# AirU_v2_1.net
KiCad netlist of a schematic drawn in EAGLE
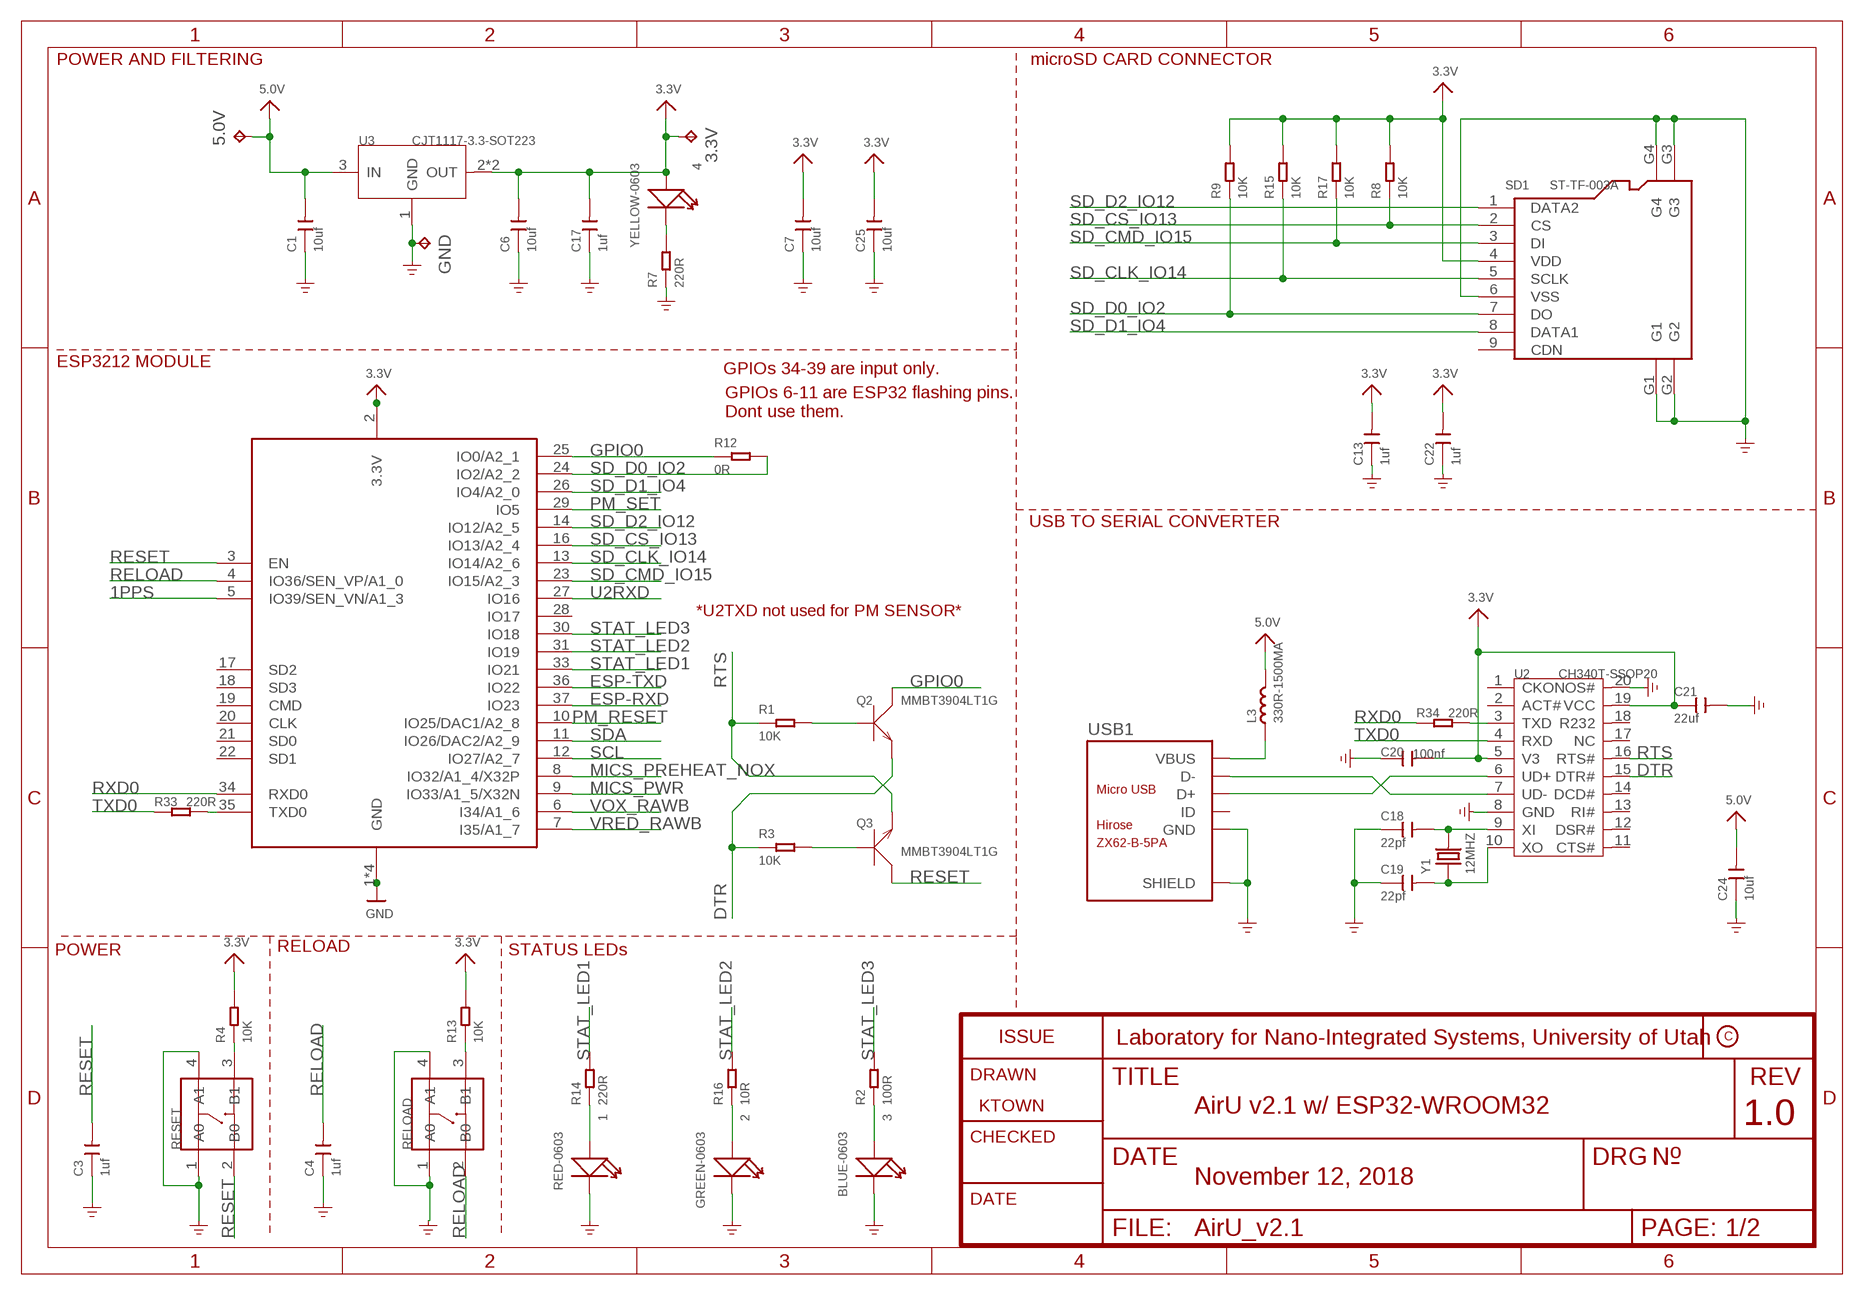
[diagram p0: schematic, sheet 1]
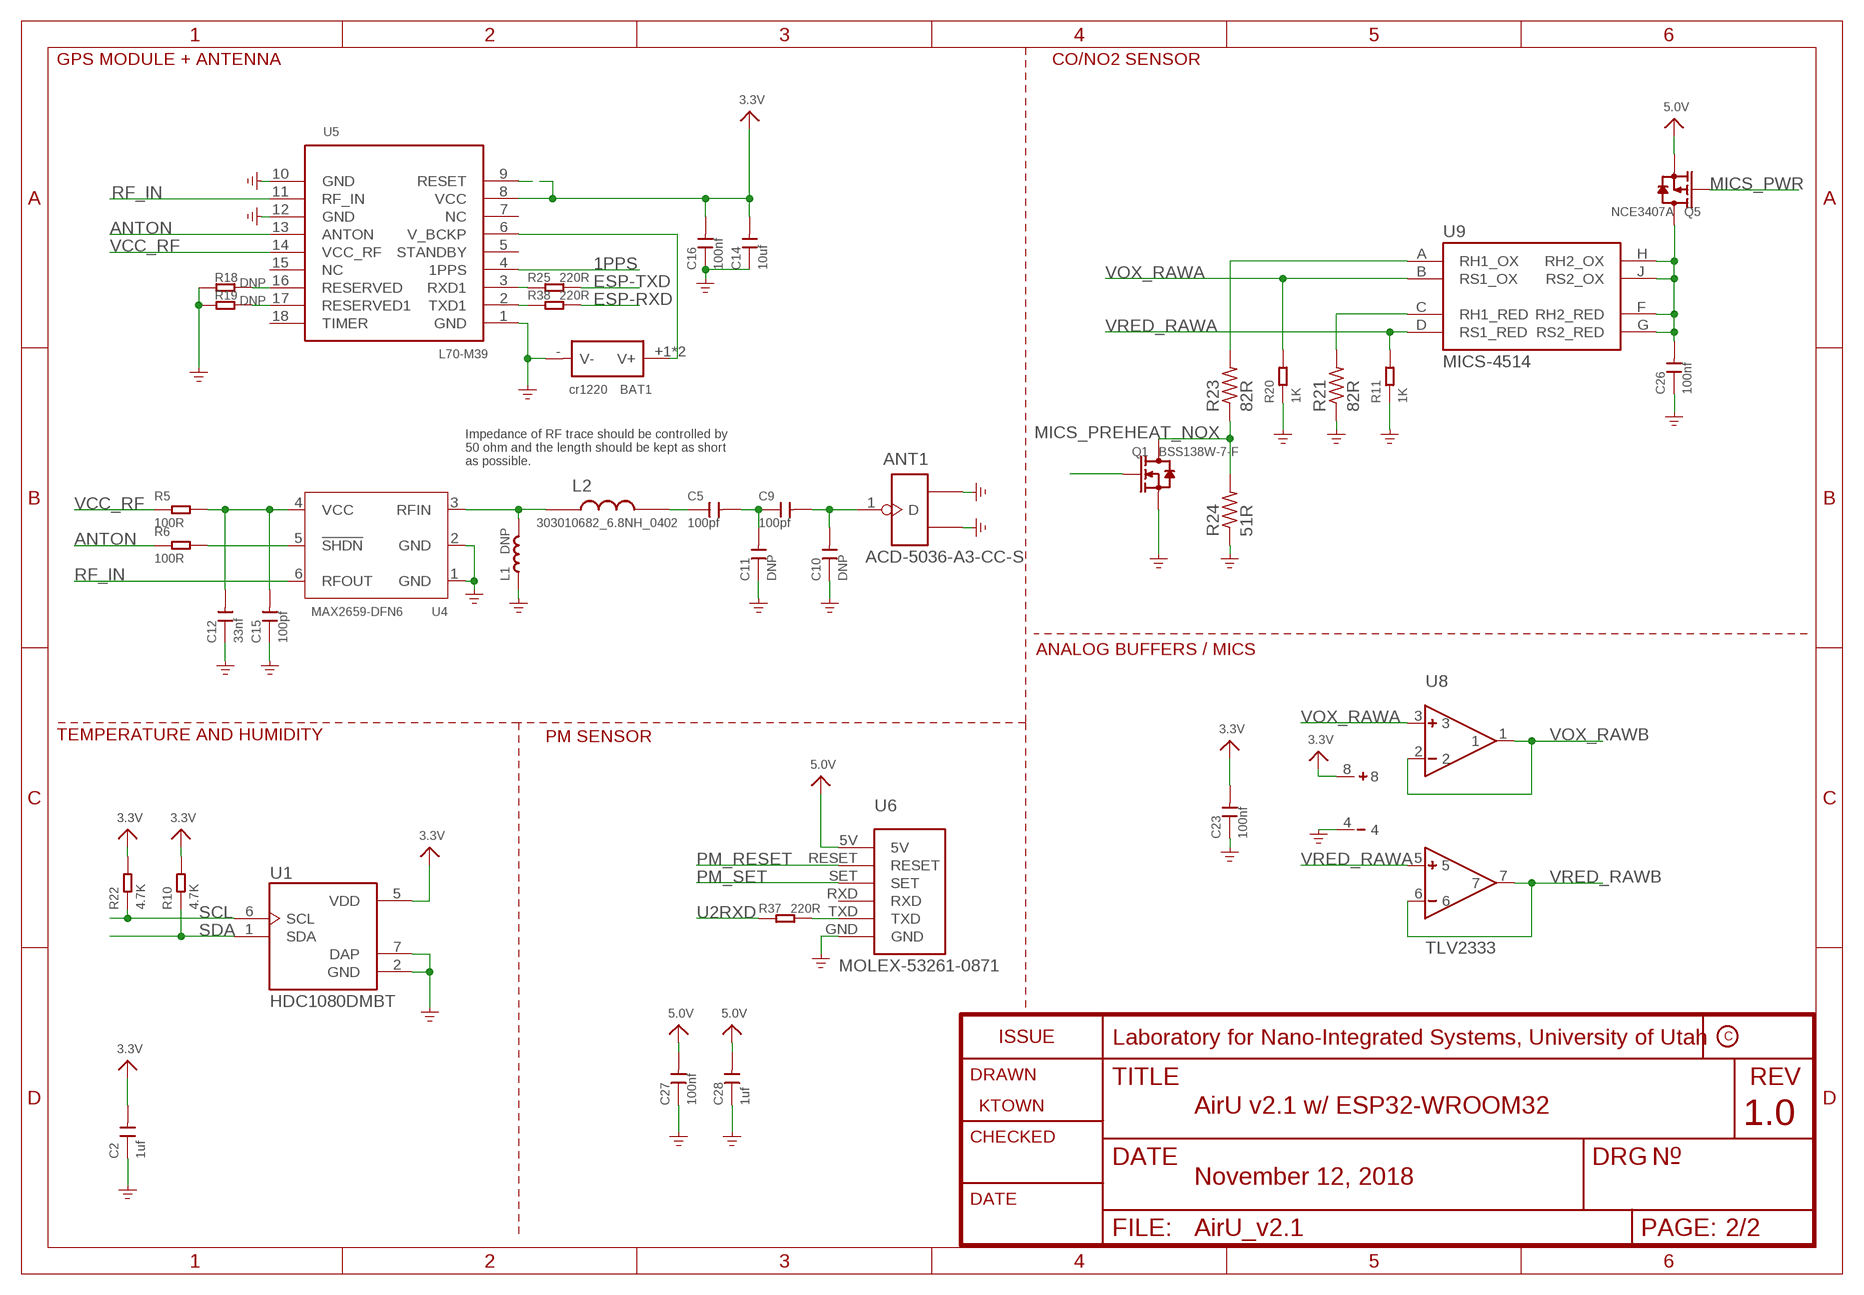
[diagram p1: schematic, sheet 2]

(export (version "E")
  (design (tool "Eeschema 10.0.6"))
  (components
    (comp (ref "1")
      (value "RED-0603")
      (footprint "eagle-import:LED-0603")
      (fields (field (name "MPN") "19-217-R6C-AL1M2VY-3T"))
      (libsource (lib "eagle-import") (part "LED-SMD-RED-DIFFUSED(0603)"))
    )
    (comp (ref "2")
      (value "GREEN-0603")
      (footprint "eagle-import:LED-0603")
      (fields (field (name "MPN") "19-217-G7C-AN1P2-3T"))
      (libsource (lib "eagle-import") (part "SMD-LED-CLEAR-GREEN(0603)"))
    )
    (comp (ref "3")
      (value "BLUE-0603")
      (footprint "eagle-import:LED-0603")
      (fields (field (name "MPN") "19-217-BHC-ZL1M2RY-3T"))
      (libsource (lib "eagle-import") (part "SMD-LED-CLEAR-BLUE(0603)"))
    )
    (comp (ref "3.3V")
      (value "TPTP20SQ")
      (footprint "eagle-import:TP20SQ")
      (libsource (lib "eagle-import") (part "TPTP20SQ"))
    )
    (comp (ref "4")
      (value "YELLOW-0603")
      (footprint "eagle-import:LED-0603")
      (fields (field (name "MPN") "19-217-Y5C-AM1N1VY-3T"))
      (libsource (lib "eagle-import") (part "SMD-LED-CLEAR-YELLOW(0603)"))
    )
    (comp (ref "5.0V")
      (value "TPTP20SQ")
      (footprint "eagle-import:TP20SQ")
      (libsource (lib "eagle-import") (part "TPTP20SQ"))
    )
    (comp (ref "C1")
      (value "10uf")
      (footprint "eagle-import:C0603")
      (fields (field (name "MPN") "CC0603KRX5R6BB106"))
      (libsource (lib "eagle-import") (part "CERAMIC-10UF-10V-10%-X5R(0603)"))
    )
    (comp (ref "C3")
      (value "1uf")
      (footprint "eagle-import:C0603")
      (fields (field (name "MPN") "CC0603KRX7R8BB105"))
      (libsource (lib "eagle-import") (part "CERAMIC-1UF-25V-10%-X7R(0603)"))
    )
    (comp (ref "C4")
      (value "1uf")
      (footprint "eagle-import:C0603")
      (fields (field (name "MPN") "CC0603KRX7R8BB105"))
      (libsource (lib "eagle-import") (part "CERAMIC-1UF-25V-10%-X7R(0603)"))
    )
    (comp (ref "C6")
      (value "10uf")
      (footprint "eagle-import:C0603")
      (fields (field (name "MPN") "CC0603KRX5R6BB106"))
      (libsource (lib "eagle-import") (part "CERAMIC-10UF-10V-10%-X5R(0603)"))
    )
    (comp (ref "C7")
      (value "10uf")
      (footprint "eagle-import:C0603")
      (fields (field (name "MPN") "CC0603KRX5R6BB106"))
      (libsource (lib "eagle-import") (part "CERAMIC-10UF-10V-10%-X5R(0603)"))
    )
    (comp (ref "C13")
      (value "1uf")
      (footprint "eagle-import:C0603")
      (fields (field (name "MPN") "CC0603KRX7R8BB105"))
      (libsource (lib "eagle-import") (part "CERAMIC-1UF-25V-10%-X7R(0603)"))
    )
    (comp (ref "C17")
      (value "1uf")
      (footprint "eagle-import:C0603")
      (fields (field (name "MPN") "CC0603KRX7R8BB105"))
      (libsource (lib "eagle-import") (part "CERAMIC-1UF-25V-10%-X7R(0603)"))
    )
    (comp (ref "C18")
      (value "22pf")
      (footprint "eagle-import:C0603")
      (fields (field (name "MPN") "CC0603JRNPO9BN220"))
      (libsource (lib "eagle-import") (part "CERAMIC-22PF-50V-5%-NPO(0603)"))
    )
    (comp (ref "C19")
      (value "22pf")
      (footprint "eagle-import:C0603")
      (fields (field (name "MPN") "CC0603JRNPO9BN220"))
      (libsource (lib "eagle-import") (part "CERAMIC-22PF-50V-5%-NPO(0603)"))
    )
    (comp (ref "C20")
      (value "100nf")
      (footprint "eagle-import:C0603")
      (fields (field (name "MPN") "CC0603KRX7R9BB104"))
      (libsource (lib "eagle-import") (part "CERAMIC-100NF-50V-10%-X7R(0603)"))
    )
    (comp (ref "C21")
      (value "22uf")
      (footprint "eagle-import:C0805")
      (fields (field (name "MPN") "CC0805MKX5R5BB226"))
      (libsource (lib "eagle-import") (part "CERAMIC-22UF-6.3V-20%-X5R(0805)"))
    )
    (comp (ref "C22")
      (value "1uf")
      (footprint "eagle-import:C0603")
      (fields (field (name "MPN") "CC0603KRX7R8BB105"))
      (libsource (lib "eagle-import") (part "CERAMIC-1UF-25V-10%-X7R(0603)"))
    )
    (comp (ref "C24")
      (value "10uf")
      (footprint "eagle-import:C0603")
      (fields (field (name "MPN") "CC0603KRX5R6BB106"))
      (libsource (lib "eagle-import") (part "CERAMIC-10UF-10V-10%-X5R(0603)"))
    )
    (comp (ref "C25")
      (value "10uf")
      (footprint "eagle-import:C0603")
      (fields (field (name "MPN") "CC0603KRX5R6BB106"))
      (libsource (lib "eagle-import") (part "CERAMIC-10UF-10V-10%-X5R(0603)"))
    )
    (comp (ref "GND")
      (value "TPTP20SQ")
      (footprint "eagle-import:TP20SQ")
      (libsource (lib "eagle-import") (part "TPTP20SQ"))
    )
    (comp (ref "L3")
      (value "330R-1500MA")
      (footprint "eagle-import:L0805")
      (fields (field (name "MPN") "BLM21PG331SN1D"))
      (libsource (lib "eagle-import") (part "SMD-FERRITE-BEAD-330R-1500MA(0805)'0805'"))
    )
    (comp (ref "Q2")
      (value "MMBT3904LT1G")
      (footprint "eagle-import:SOT-23")
      (libsource (lib "eagle-import") (part "SMD-TRANSISTORS-NPN-40V-200MA-MMBT3904LT1G(SOT-23)"))
    )
    (comp (ref "Q3")
      (value "MMBT3904LT1G")
      (footprint "eagle-import:SOT-23")
      (libsource (lib "eagle-import") (part "SMD-TRANSISTORS-NPN-40V-200MA-MMBT3904LT1G(SOT-23)"))
    )
    (comp (ref "R1")
      (value "10K")
      (footprint "eagle-import:R0603")
      (fields (field (name "MPN") "RC0603FR-0710KL"))
      (libsource (lib "eagle-import") (part "SMD-RES-10K-1%-1/10W(0603)"))
    )
    (comp (ref "R2")
      (value "100R")
      (footprint "eagle-import:R0603")
      (fields (field (name "MPN") "RC0603JR-07100RL"))
      (libsource (lib "eagle-import") (part "SMD-RES-100R-5%-1/10W(0603)"))
    )
    (comp (ref "R3")
      (value "10K")
      (footprint "eagle-import:R0603")
      (fields (field (name "MPN") "RC0603FR-0710KL"))
      (libsource (lib "eagle-import") (part "SMD-RES-10K-1%-1/10W(0603)"))
    )
    (comp (ref "R4")
      (value "10K")
      (footprint "eagle-import:R0603")
      (fields (field (name "MPN") "RC0603FR-0710KL"))
      (libsource (lib "eagle-import") (part "SMD-RES-10K-1%-1/10W(0603)"))
    )
    (comp (ref "R7")
      (value "220R")
      (footprint "eagle-import:R0603")
      (fields (field (name "MPN") "RC0603JR-07220RL"))
      (libsource (lib "eagle-import") (part "SMD-RES-220R-5%-1/10W(0603)"))
    )
    (comp (ref "R8")
      (value "10K")
      (footprint "eagle-import:R0603")
      (fields (field (name "MPN") "RC0603FR-0710KL"))
      (libsource (lib "eagle-import") (part "SMD-RES-10K-1%-1/10W(0603)"))
    )
    (comp (ref "R9")
      (value "10K")
      (footprint "eagle-import:R0603")
      (fields (field (name "MPN") "RC0603FR-0710KL"))
      (libsource (lib "eagle-import") (part "SMD-RES-10K-1%-1/10W(0603)"))
    )
    (comp (ref "R12")
      (value "0R")
      (footprint "eagle-import:R0603")
      (fields (field (name "MPN") "RC0603JR-070RL"))
      (libsource (lib "eagle-import") (part "SMD-RES-0R-5%-1/10W(0603)"))
    )
    (comp (ref "R13")
      (value "10K")
      (footprint "eagle-import:R0603")
      (fields (field (name "MPN") "RC0603FR-0710KL"))
      (libsource (lib "eagle-import") (part "SMD-RES-10K-1%-1/10W(0603)"))
    )
    (comp (ref "R14")
      (value "220R")
      (footprint "eagle-import:R0603")
      (fields (field (name "MPN") "RC0603JR-07220RL"))
      (libsource (lib "eagle-import") (part "SMD-RES-220R-5%-1/10W(0603)"))
    )
    (comp (ref "R15")
      (value "10K")
      (footprint "eagle-import:R0603")
      (fields (field (name "MPN") "RC0603FR-0710KL"))
      (libsource (lib "eagle-import") (part "SMD-RES-10K-1%-1/10W(0603)"))
    )
    (comp (ref "R16")
      (value "10R")
      (footprint "eagle-import:R0603")
      (fields (field (name "MPN") "RC0603JR-0710RL"))
      (libsource (lib "eagle-import") (part "SMD-RES-10R-5%-1/10W(0603)"))
    )
    (comp (ref "R17")
      (value "10K")
      (footprint "eagle-import:R0603")
      (fields (field (name "MPN") "RC0603FR-0710KL"))
      (libsource (lib "eagle-import") (part "SMD-RES-10K-1%-1/10W(0603)"))
    )
    (comp (ref "R33")
      (value "220R")
      (footprint "eagle-import:R0603")
      (fields (field (name "MPN") "RC0603JR-07220RL"))
      (libsource (lib "eagle-import") (part "SMD-RES-220R-5%-1/10W(0603)"))
    )
    (comp (ref "R34")
      (value "220R")
      (footprint "eagle-import:R0603")
      (fields (field (name "MPN") "RC0603JR-07220RL"))
      (libsource (lib "eagle-import") (part "SMD-RES-220R-5%-1/10W(0603)"))
    )
    (comp (ref "RELOAD")
      (value "DIP-SWITCH-TACTILE-SPST-NO/TS-1109(4P-D6.0MM)'TS-1109'")
      (footprint "eagle-import:SW4-6.0X6.0X5.0MM")
      (libsource (lib "eagle-import") (part "DIP-SWITCH-TACTILE-SPST-NO/TS-1109(4P-D6.0MM)'TS-1109'"))
    )
    (comp (ref "RESET")
      (value "DIP-SWITCH-TACTILE-SPST-NO/TS-1109(4P-D6.0MM)'TS-1109'")
      (footprint "eagle-import:SW4-6.0X6.0X5.0MM")
      (libsource (lib "eagle-import") (part "DIP-SWITCH-TACTILE-SPST-NO/TS-1109(4P-D6.0MM)'TS-1109'"))
    )
    (comp (ref "SD1")
      (value "ST-TF-003A")
      (footprint "eagle-import:MICRO-SD9+4P-SMD-16.1X14.5X1.85MM")
      (libsource (lib "eagle-import") (part "MICRO-SD-CARD-SOCKET-9P(ST-TF-003A)"))
    )
    (comp (ref "U2")
      (value "CH340T-SSOP20")
      (footprint "eagle-import:SSOP20-0.65-7.6X5.2MM")
      (fields (field (name "MPN") "CH340T"))
      (libsource (lib "eagle-import") (part "INTERFACE-CH340T(SSOP20)"))
    )
    (comp (ref "U3")
      (value "CJT1117-3.3-SOT223")
      (footprint "eagle-import:SOT-223")
      (fields (field (name "MPN") "CJT1117-3.3"))
      (libsource (lib "eagle-import") (part "PMIC-CJT1117-3.3(SOT223)"))
    )
    (comp (ref "U7")
      (value "ESP32_WROOM32_SKINNY")
      (footprint "eagle-import:WROOM32_SKINNY")
      (libsource (lib "eagle-import") (part "ESP32_WROOM32_SKINNY"))
    )
    (comp (ref "USB1")
      (value "ZX62-B-5PA")
      (footprint "eagle-import:MICRO-USB5+6P-SMD-0.65-AB")
      (libsource (lib "eagle-import") (part "MICRO-USB-SMD(ZX62-B-5PA)"))
    )
    (comp (ref "Y1")
      (value "12MHZ")
      (footprint "eagle-import:X2-SMD-5.0X3.2X1.3MM")
      (fields (field (name "MPN") "5032/2P"))
      (libsource (lib "eagle-import") (part "SMD-CRYSTAL-12MHZ-20PF-20PPM-40R(2P-5.0X3.2MM)"))
    )
    (comp (ref "ANT1")
      (value "ACD-5036-A3-CC-S")
      (footprint "eagle-import:ANT3-SMD-5.2X3.7X0.7MM")
      (libsource (lib "eagle-import") (part "ANTENNA-ACD5036"))
    )
    (comp (ref "BAT1")
      (value "cr1220")
      (footprint "eagle-import:BAT2P-13.5-CR1220")
      (libsource (lib "eagle-import") (part "DIP-BATTERY-CELL-HOLDER(1220)"))
    )
    (comp (ref "C2")
      (value "1uf")
      (footprint "eagle-import:C0603")
      (fields (field (name "MPN") "CC0603KRX7R8BB105"))
      (libsource (lib "eagle-import") (part "CERAMIC-1UF-25V-10%-X7R(0603)"))
    )
    (comp (ref "C5")
      (value "100pf")
      (footprint "eagle-import:C0603")
      (fields (field (name "MPN") "CC0603JRNPO9BN101"))
      (libsource (lib "eagle-import") (part "CERAMIC-100PF-50V-5%-NPO(0603)"))
    )
    (comp (ref "C9")
      (value "100pf")
      (footprint "eagle-import:C0603")
      (fields (field (name "MPN") "CC0603JRNPO9BN101"))
      (libsource (lib "eagle-import") (part "CERAMIC-100PF-50V-5%-NPO(0603)"))
    )
    (comp (ref "C10")
      (value "DNP")
      (footprint "eagle-import:C0603")
      (fields (field (name "MPN") "CC0603JRNPO9BN101"))
      (libsource (lib "eagle-import") (part "CERAMIC-100PF-50V-5%-NPO(0603)"))
    )
    (comp (ref "C11")
      (value "DNP")
      (footprint "eagle-import:C0603")
      (fields (field (name "MPN") "CC0603JRNPO9BN101"))
      (libsource (lib "eagle-import") (part "CERAMIC-100PF-50V-5%-NPO(0603)"))
    )
    (comp (ref "C12")
      (value "33nf")
      (footprint "eagle-import:C0603")
      (fields (field (name "MPN") "CC0603KRX7R9BB333"))
      (libsource (lib "eagle-import") (part "CERAMIC-33NF-50V-10%-X7R(0603)"))
    )
    (comp (ref "C14")
      (value "10uf")
      (footprint "eagle-import:C0603")
      (fields (field (name "MPN") "CC0603KRX5R6BB106"))
      (libsource (lib "eagle-import") (part "CERAMIC-10UF-10V-10%-X5R(0603)"))
    )
    (comp (ref "C15")
      (value "100pf")
      (footprint "eagle-import:C0603")
      (fields (field (name "MPN") "CC0603JRNPO9BN101"))
      (libsource (lib "eagle-import") (part "CERAMIC-100PF-50V-5%-NPO(0603)"))
    )
    (comp (ref "C16")
      (value "100nf")
      (footprint "eagle-import:C0603")
      (fields (field (name "MPN") "CC0603KRX7R9BB104"))
      (libsource (lib "eagle-import") (part "CERAMIC-100NF-50V-10%-X7R(0603)"))
    )
    (comp (ref "C23")
      (value "100nf")
      (footprint "eagle-import:C0603")
      (fields (field (name "MPN") "CC0603KRX7R9BB104"))
      (libsource (lib "eagle-import") (part "CERAMIC-100NF-50V-10%-X7R(0603)"))
    )
    (comp (ref "C26")
      (value "100nf")
      (footprint "eagle-import:C0603")
      (fields (field (name "MPN") "CC0603KRX7R9BB104"))
      (libsource (lib "eagle-import") (part "CERAMIC-100NF-50V-10%-X7R(0603)"))
    )
    (comp (ref "C27")
      (value "100nf")
      (footprint "eagle-import:C0603")
      (fields (field (name "MPN") "CC0603KRX7R9BB104"))
      (libsource (lib "eagle-import") (part "CERAMIC-100NF-50V-10%-X7R(0603)"))
    )
    (comp (ref "C28")
      (value "1uf")
      (footprint "eagle-import:C0603")
      (fields (field (name "MPN") "CC0603KRX7R8BB105"))
      (libsource (lib "eagle-import") (part "CERAMIC-1UF-25V-10%-X7R(0603)"))
    )
    (comp (ref "L1")
      (value "DNP")
      (footprint "eagle-import:L0201")
      (libsource (lib "eagle-import") (part "INDUCTOR/FERRITE-BEAD-0201"))
    )
    (comp (ref "L2")
      (value "303010682_6.8NH_0402")
      (footprint "eagle-import:L0402")
      (libsource (lib "eagle-import") (part "303010682_6.8NH_0402"))
    )
    (comp (ref "Q1")
      (value "BSS138W-7-F")
      (footprint "eagle-import:SOT-23")
      (libsource (lib "eagle-import") (part "SMD-MOSFET-N-CH-50V-200MA-BSS138W-7-F(SOT-23)"))
    )
    (comp (ref "Q5")
      (value "NCE3407A")
      (footprint "eagle-import:SOT-23")
      (libsource (lib "eagle-import") (part "SMD-MOSFET-P-CH-VDC=30V-ID=4.3A-NCE3407A(SOT-23)"))
    )
    (comp (ref "R5")
      (value "100R")
      (footprint "eagle-import:R0603")
      (fields (field (name "MPN") "RC0603JR-07100RL"))
      (libsource (lib "eagle-import") (part "SMD-RES-100R-5%-1/10W(0603)"))
    )
    (comp (ref "R6")
      (value "100R")
      (footprint "eagle-import:R0603")
      (fields (field (name "MPN") "RC0603JR-07100RL"))
      (libsource (lib "eagle-import") (part "SMD-RES-100R-5%-1/10W(0603)"))
    )
    (comp (ref "R10")
      (value "4.7K")
      (footprint "eagle-import:R0603")
      (fields (field (name "MPN") "RC0603JR-074K7L"))
      (libsource (lib "eagle-import") (part "SMD-RES-4.7K-5%-1/10W(0603)"))
    )
    (comp (ref "R11")
      (value "1K")
      (footprint "eagle-import:R0603")
      (fields (field (name "MPN") "RC0603FR-071KL"))
      (libsource (lib "eagle-import") (part "SMD-RES-1K-1%-1/10W(0603)"))
    )
    (comp (ref "R18")
      (value "DNP")
      (footprint "eagle-import:R0603")
      (fields (field (name "MPN") "RC0603FR-0710KL"))
      (libsource (lib "eagle-import") (part "SMD-RES-10K-1%-1/10W(0603)"))
    )
    (comp (ref "R19")
      (value "DNP")
      (footprint "eagle-import:R0603")
      (fields (field (name "MPN") "RC0603FR-0710KL"))
      (libsource (lib "eagle-import") (part "SMD-RES-10K-1%-1/10W(0603)"))
    )
    (comp (ref "R20")
      (value "1K")
      (footprint "eagle-import:R0603")
      (fields (field (name "MPN") "RC0603FR-071KL"))
      (libsource (lib "eagle-import") (part "SMD-RES-1K-1%-1/10W(0603)"))
    )
    (comp (ref "R21")
      (value "82R")
      (footprint "eagle-import:R0603")
      (libsource (lib "eagle-import") (part "R-US_R0603"))
    )
    (comp (ref "R22")
      (value "4.7K")
      (footprint "eagle-import:R0603")
      (fields (field (name "MPN") "RC0603JR-074K7L"))
      (libsource (lib "eagle-import") (part "SMD-RES-4.7K-5%-1/10W(0603)"))
    )
    (comp (ref "R23")
      (value "82R")
      (footprint "eagle-import:R0603")
      (libsource (lib "eagle-import") (part "R-US_R0603"))
    )
    (comp (ref "R24")
      (value "51R")
      (footprint "eagle-import:R0603")
      (libsource (lib "eagle-import") (part "R-US_R0603"))
    )
    (comp (ref "R25")
      (value "220R")
      (footprint "eagle-import:R0603")
      (fields (field (name "MPN") "RC0603JR-07220RL"))
      (libsource (lib "eagle-import") (part "SMD-RES-220R-5%-1/10W(0603)"))
    )
    (comp (ref "R37")
      (value "220R")
      (footprint "eagle-import:R0603")
      (fields (field (name "MPN") "RC0603JR-07220RL"))
      (libsource (lib "eagle-import") (part "SMD-RES-220R-5%-1/10W(0603)"))
    )
    (comp (ref "R38")
      (value "220R")
      (footprint "eagle-import:R0603")
      (fields (field (name "MPN") "RC0603JR-07220RL"))
      (libsource (lib "eagle-import") (part "SMD-RES-220R-5%-1/10W(0603)"))
    )
    (comp (ref "U1")
      (value "HDC1080DMBT")
      (footprint "eagle-import:SON100P300X300X80-7N")
      (fields (field (name "DIGI-KEY_PART_NUMBER") "296-43864-1-ND") (field (name "MF") "Texas Instruments"))
      (libsource (lib "eagle-import") (part "HDC1080DMBT"))
    )
    (comp (ref "U4")
      (value "MAX2659-DFN6")
      (footprint "eagle-import:DFN6-0.5-1.5X1.2X0.72MM")
      (fields (field (name "MPN") "MAX2659"))
      (libsource (lib "eagle-import") (part "AMPLIFIER-MAX2659"))
    )
    (comp (ref "U5")
      (value "L70-M39")
      (footprint "eagle-import:LGA18-1.1-9.7X10.1X2.5MM")
      (fields (field (name "MPN") "L70"))
      (libsource (lib "eagle-import") (part "MOUDLE-GPS-L70-HARDWARE"))
    )
    (comp (ref "U6")
      (value "MOLEX-53261-0871")
      (footprint "eagle-import:MOLEX-53261-0871")
      (libsource (lib "eagle-import") (part "MOLEX-53261-0871"))
    )
    (comp (ref "U8")
      (value "TLV2333")
      (footprint "eagle-import:TLV2333")
      (libsource (lib "eagle-import") (part "TLV2333"))
    )
    (comp (ref "U9")
      (value "MICS-4514")
      (footprint "eagle-import:MICS_10-SMD")
      (fields (field (name "MF") "Amphenol"))
      (libsource (lib "eagle-import") (part "MICS-4514"))
    )
  )
  (nets
    (net (code "1") (name "1PPS") (class "Default")
      (node (ref "U5") (pin "4") (pinfunction "1PPS_4") (pintype "bidirectional"))
      (node (ref "U7") (pin "5") (pinfunction "IO39/SEN_VN/A1_3_5") (pintype "passive"))
    )
    (net (code "2") (name "3.3V") (class "Default")
      (node (ref "3.3V") (pin "TP") (pinfunction "TP_TP") (pintype "input"))
      (node (ref "4") (pin "+") (pinfunction "+_+") (pintype "passive"))
      (node (ref "C13") (pin "2") (pinfunction "2_2") (pintype "passive"))
      (node (ref "C14") (pin "2") (pinfunction "2_2") (pintype "passive"))
      (node (ref "C16") (pin "2") (pinfunction "2_2") (pintype "passive"))
      (node (ref "C17") (pin "2") (pinfunction "2_2") (pintype "passive"))
      (node (ref "C2") (pin "2") (pinfunction "2_2") (pintype "passive"))
      (node (ref "C20") (pin "2") (pinfunction "2_2") (pintype "passive"))
      (node (ref "C21") (pin "1") (pinfunction "1_1") (pintype "passive"))
      (node (ref "C22") (pin "2") (pinfunction "2_2") (pintype "passive"))
      (node (ref "C23") (pin "2") (pinfunction "2_2") (pintype "passive"))
      (node (ref "C25") (pin "2") (pinfunction "2_2") (pintype "passive"))
      (node (ref "C6") (pin "2") (pinfunction "2_2") (pintype "passive"))
      (node (ref "C7") (pin "2") (pinfunction "2_2") (pintype "passive"))
      (node (ref "R10") (pin "2") (pinfunction "2_2") (pintype "passive"))
      (node (ref "R13") (pin "2") (pinfunction "2_2") (pintype "passive"))
      (node (ref "R15") (pin "2") (pinfunction "2_2") (pintype "passive"))
      (node (ref "R17") (pin "2") (pinfunction "2_2") (pintype "passive"))
      (node (ref "R22") (pin "2") (pinfunction "2_2") (pintype "passive"))
      (node (ref "R4") (pin "2") (pinfunction "2_2") (pintype "passive"))
      (node (ref "R8") (pin "2") (pinfunction "2_2") (pintype "passive"))
      (node (ref "R9") (pin "2") (pinfunction "2_2") (pintype "passive"))
      (node (ref "SD1") (pin "4") (pinfunction "VDD_4") (pintype "bidirectional"))
      (node (ref "U1") (pin "5") (pinfunction "VDD_5") (pintype "power_in"))
      (node (ref "U2") (pin "19") (pinfunction "VCC_19") (pintype "power_in"))
      (node (ref "U2") (pin "5") (pinfunction "V3_5") (pintype "power_in"))
      (node (ref "U3") (pin "2") (pinfunction "OUT_2") (pintype "bidirectional"))
      (node (ref "U3") (pin "TER") (pinfunction "OUT_TER") (pintype "bidirectional"))
      (node (ref "U5") (pin "8") (pinfunction "VCC_8") (pintype "power_in"))
      (node (ref "U5") (pin "9") (pinfunction "RESET_9") (pintype "bidirectional"))
      (node (ref "U7") (pin "2") (pinfunction "3.3V_2") (pintype "passive"))
      (node (ref "U8") (pin "8") (pinfunction "8_8") (pintype "bidirectional"))
    )
    (net (code "3") (name "5.0V") (class "Default")
      (node (ref "5.0V") (pin "TP") (pinfunction "TP_TP") (pintype "input"))
      (node (ref "C1") (pin "2") (pinfunction "2_2") (pintype "passive"))
      (node (ref "C24") (pin "2") (pinfunction "2_2") (pintype "passive"))
      (node (ref "C27") (pin "2") (pinfunction "2_2") (pintype "passive"))
      (node (ref "C28") (pin "2") (pinfunction "2_2") (pintype "passive"))
      (node (ref "L3") (pin "2") (pinfunction "2_2") (pintype "passive"))
      (node (ref "Q5") (pin "2") (pinfunction "S_2") (pintype "passive"))
      (node (ref "U3") (pin "3") (pinfunction "IN_3") (pintype "bidirectional"))
      (node (ref "U6") (pin "5V") (pinfunction "5V_5V") (pintype "bidirectional"))
    )
    (net (code "4") (name "ANTON") (class "Default")
      (node (ref "R6") (pin "1") (pinfunction "1_1") (pintype "passive"))
      (node (ref "U5") (pin "13") (pinfunction "ANTON_13") (pintype "bidirectional"))
    )
    (net (code "5") (name "DTR") (class "Default")
      (node (ref "Q2") (pin "2") (pinfunction "E_2") (pintype "passive"))
      (node (ref "R3") (pin "1") (pinfunction "1_1") (pintype "passive"))
      (node (ref "U2") (pin "15") (pinfunction "DTR#_15") (pintype "output"))
    )
    (net (code "6") (name "ESP-RXD") (class "Default")
      (node (ref "R38") (pin "2") (pinfunction "2_2") (pintype "passive"))
      (node (ref "U7") (pin "37") (pinfunction "IO23_37") (pintype "bidirectional"))
    )
    (net (code "7") (name "ESP-TXD") (class "Default")
      (node (ref "R25") (pin "2") (pinfunction "2_2") (pintype "passive"))
      (node (ref "U7") (pin "36") (pinfunction "IO22_36") (pintype "bidirectional"))
    )
    (net (code "8") (name "GND") (class "Default")
      (node (ref "1") (pin "-") (pinfunction "-_-") (pintype "passive"))
      (node (ref "2") (pin "-") (pinfunction "-_-") (pintype "passive"))
      (node (ref "3") (pin "-") (pinfunction "-_-") (pintype "passive"))
      (node (ref "ANT1") (pin "2") (pinfunction "GND1_2") (pintype "bidirectional"))
      (node (ref "ANT1") (pin "3") (pinfunction "GND2_3") (pintype "bidirectional"))
      (node (ref "BAT1") (pin "-") (pinfunction "V-_-") (pintype "bidirectional"))
      (node (ref "C1") (pin "1") (pinfunction "1_1") (pintype "passive"))
      (node (ref "C10") (pin "1") (pinfunction "1_1") (pintype "passive"))
      (node (ref "C11") (pin "1") (pinfunction "1_1") (pintype "passive"))
      (node (ref "C12") (pin "1") (pinfunction "1_1") (pintype "passive"))
      (node (ref "C13") (pin "1") (pinfunction "1_1") (pintype "passive"))
      (node (ref "C14") (pin "1") (pinfunction "1_1") (pintype "passive"))
      (node (ref "C15") (pin "1") (pinfunction "1_1") (pintype "passive"))
      (node (ref "C16") (pin "1") (pinfunction "1_1") (pintype "passive"))
      (node (ref "C17") (pin "1") (pinfunction "1_1") (pintype "passive"))
      (node (ref "C18") (pin "1") (pinfunction "1_1") (pintype "passive"))
      (node (ref "C19") (pin "1") (pinfunction "1_1") (pintype "passive"))
      (node (ref "C2") (pin "1") (pinfunction "1_1") (pintype "passive"))
      (node (ref "C20") (pin "1") (pinfunction "1_1") (pintype "passive"))
      (node (ref "C21") (pin "2") (pinfunction "2_2") (pintype "passive"))
      (node (ref "C22") (pin "1") (pinfunction "1_1") (pintype "passive"))
      (node (ref "C23") (pin "1") (pinfunction "1_1") (pintype "passive"))
      (node (ref "C24") (pin "1") (pinfunction "1_1") (pintype "passive"))
      (node (ref "C25") (pin "1") (pinfunction "1_1") (pintype "passive"))
      (node (ref "C26") (pin "1") (pinfunction "1_1") (pintype "passive"))
      (node (ref "C27") (pin "1") (pinfunction "1_1") (pintype "passive"))
      (node (ref "C28") (pin "1") (pinfunction "1_1") (pintype "passive"))
      (node (ref "C3") (pin "1") (pinfunction "1_1") (pintype "passive"))
      (node (ref "C4") (pin "1") (pinfunction "1_1") (pintype "passive"))
      (node (ref "C6") (pin "1") (pinfunction "1_1") (pintype "passive"))
      (node (ref "C7") (pin "1") (pinfunction "1_1") (pintype "passive"))
      (node (ref "GND") (pin "TP") (pinfunction "TP_TP") (pintype "input"))
      (node (ref "L1") (pin "1") (pinfunction "1_1") (pintype "passive"))
      (node (ref "Q1") (pin "2") (pinfunction "S_2") (pintype "passive"))
      (node (ref "R11") (pin "1") (pinfunction "1_1") (pintype "passive"))
      (node (ref "R18") (pin "1") (pinfunction "1_1") (pintype "passive"))
      (node (ref "R19") (pin "1") (pinfunction "1_1") (pintype "passive"))
      (node (ref "R20") (pin "1") (pinfunction "1_1") (pintype "passive"))
      (node (ref "R21") (pin "1") (pinfunction "1_1") (pintype "passive"))
      (node (ref "R24") (pin "1") (pinfunction "1_1") (pintype "passive"))
      (node (ref "R7") (pin "1") (pinfunction "1_1") (pintype "passive"))
      (node (ref "RELOAD") (pin "1") (pinfunction "A0_1") (pintype "bidirectional"))
      (node (ref "RELOAD") (pin "4") (pinfunction "A1_4") (pintype "bidirectional"))
      (node (ref "RESET") (pin "1") (pinfunction "A0_1") (pintype "bidirectional"))
      (node (ref "RESET") (pin "4") (pinfunction "A1_4") (pintype "bidirectional"))
      (node (ref "SD1") (pin "6") (pinfunction "VSS_6") (pintype "bidirectional"))
      (node (ref "SD1") (pin "G1") (pinfunction "G1_G1") (pintype "bidirectional"))
      (node (ref "SD1") (pin "G2") (pinfunction "G2_G2") (pintype "bidirectional"))
      (node (ref "SD1") (pin "G3") (pinfunction "G3_G3") (pintype "bidirectional"))
      (node (ref "SD1") (pin "G4") (pinfunction "G4_G4") (pintype "bidirectional"))
      (node (ref "U1") (pin "2") (pinfunction "GND_2") (pintype "power_in"))
      (node (ref "U1") (pin "7") (pinfunction "DAP_7") (pintype "power_in"))
      (node (ref "U2") (pin "20") (pinfunction "NOS#_20") (pintype "power_in"))
      (node (ref "U2") (pin "8") (pinfunction "GND_8") (pintype "power_in"))
      (node (ref "U3") (pin "1") (pinfunction "GND_1") (pintype "bidirectional"))
      (node (ref "U4") (pin "1") (pinfunction "GND_1") (pintype "power_in"))
      (node (ref "U4") (pin "2") (pinfunction "GND_2") (pintype "power_in"))
      (node (ref "U5") (pin "1") (pinfunction "GND_1") (pintype "power_in"))
      (node (ref "U5") (pin "10") (pinfunction "GND_10") (pintype "power_in"))
      (node (ref "U5") (pin "12") (pinfunction "GND_12") (pintype "bidirectional"))
      (node (ref "U6") (pin "GND") (pinfunction "GND_GND") (pintype "bidirectional"))
      (node (ref "U7") (pin "1") (pinfunction "GND_1") (pintype "passive"))
      (node (ref "U7") (pin "15") (pinfunction "GND_15") (pintype "passive"))
      (node (ref "U7") (pin "38") (pinfunction "GND_38") (pintype "passive"))
      (node (ref "U7") (pin "P$1") (pinfunction "GND_P$1") (pintype "passive"))
      (node (ref "U8") (pin "4") (pinfunction "4_4") (pintype "bidirectional"))
      (node (ref "USB1") (pin "5") (pinfunction "GND_5") (pintype "power_in"))
      (node (ref "USB1") (pin "P1") (pinfunction "SHIELD_P1") (pintype "power_in"))
      (node (ref "USB1") (pin "P2") (pinfunction "SHIELD_P2") (pintype "power_in"))
      (node (ref "USB1") (pin "P3_1") (pinfunction "SHIELD_P3_1") (pintype "power_in"))
      (node (ref "USB1") (pin "P3_2") (pinfunction "SHIELD_P3_2") (pintype "power_in"))
      (node (ref "USB1") (pin "P3_3") (pinfunction "SHIELD_P3_3") (pintype "power_in"))
      (node (ref "USB1") (pin "P4_1") (pinfunction "SHIELD_P4_1") (pintype "power_in"))
      (node (ref "USB1") (pin "P4_2") (pinfunction "SHIELD_P4_2") (pintype "power_in"))
      (node (ref "USB1") (pin "P4_3") (pinfunction "SHIELD_P4_3") (pintype "power_in"))
      (node (ref "USB1") (pin "P5") (pinfunction "SHIELD_P5") (pintype "power_in"))
      (node (ref "USB1") (pin "P6") (pinfunction "SHIELD_P6") (pintype "power_in"))
    )
    (net (code "9") (name "GPIO0") (class "Default")
      (node (ref "Q2") (pin "3") (pinfunction "C_3") (pintype "passive"))
      (node (ref "R12") (pin "1") (pinfunction "1_1") (pintype "passive"))
      (node (ref "U7") (pin "25") (pinfunction "IO0/A2_1_25") (pintype "bidirectional"))
    )
    (net (code "10") (name "MICS_PREHEAT_NOX") (class "Default")
      (node (ref "Q1") (pin "1") (pinfunction "G_1") (pintype "passive"))
      (node (ref "U7") (pin "8") (pinfunction "IO32/A1_4/X32P_8") (pintype "bidirectional"))
    )
    (net (code "11") (name "MICS_PWR") (class "Default")
      (node (ref "Q5") (pin "1") (pinfunction "G_1") (pintype "passive"))
      (node (ref "U7") (pin "9") (pinfunction "IO33/A1_5/X32N_9") (pintype "bidirectional"))
    )
    (net (code "12") (name "Net-(1-Pad+)") (class "Default")
      (node (ref "1") (pin "+") (pinfunction "+_+") (pintype "passive"))
      (node (ref "R14") (pin "1") (pinfunction "1_1") (pintype "passive"))
    )
    (net (code "13") (name "Net-(2-Pad+)") (class "Default")
      (node (ref "2") (pin "+") (pinfunction "+_+") (pintype "passive"))
      (node (ref "R16") (pin "1") (pinfunction "1_1") (pintype "passive"))
    )
    (net (code "14") (name "Net-(3-Pad+)") (class "Default")
      (node (ref "3") (pin "+") (pinfunction "+_+") (pintype "passive"))
      (node (ref "R2") (pin "1") (pinfunction "1_1") (pintype "passive"))
    )
    (net (code "15") (name "Net-(4-Pad-)") (class "Default")
      (node (ref "4") (pin "-") (pinfunction "-_-") (pintype "passive"))
      (node (ref "R7") (pin "2") (pinfunction "2_2") (pintype "passive"))
    )
    (net (code "16") (name "Net-(ANT1-D)") (class "Default")
      (node (ref "ANT1") (pin "1") (pinfunction "D_1") (pintype "bidirectional"))
      (node (ref "C10") (pin "2") (pinfunction "2_2") (pintype "passive"))
      (node (ref "C9") (pin "2") (pinfunction "2_2") (pintype "passive"))
    )
    (net (code "17") (name "Net-(C5-Pad1)") (class "Default")
      (node (ref "C5") (pin "1") (pinfunction "1_1") (pintype "passive"))
      (node (ref "L2") (pin "P$2") (pinfunction "P$2_P$2") (pintype "passive"))
    )
    (net (code "18") (name "Net-(C11-Pad2)") (class "Default")
      (node (ref "C11") (pin "2") (pinfunction "2_2") (pintype "passive"))
      (node (ref "C5") (pin "2") (pinfunction "2_2") (pintype "passive"))
      (node (ref "C9") (pin "1") (pinfunction "1_1") (pintype "passive"))
    )
    (net (code "19") (name "Net-(Q1-D)") (class "Default")
      (node (ref "Q1") (pin "3") (pinfunction "D_3") (pintype "passive"))
      (node (ref "R23") (pin "1") (pinfunction "1_1") (pintype "passive"))
      (node (ref "R24") (pin "2") (pinfunction "2_2") (pintype "passive"))
    )
    (net (code "20") (name "Net-(Q2-B)") (class "Default")
      (node (ref "Q2") (pin "1") (pinfunction "B_1") (pintype "passive"))
      (node (ref "R1") (pin "2") (pinfunction "2_2") (pintype "passive"))
    )
    (net (code "21") (name "Net-(Q3-B)") (class "Default")
      (node (ref "Q3") (pin "1") (pinfunction "B_1") (pintype "passive"))
      (node (ref "R3") (pin "2") (pinfunction "2_2") (pintype "passive"))
    )
    (net (code "22") (name "Net-(Q5-D)") (class "Default")
      (node (ref "C26") (pin "2") (pinfunction "2_2") (pintype "passive"))
      (node (ref "Q5") (pin "3") (pinfunction "D_3") (pintype "passive"))
      (node (ref "U9") (pin "F") (pinfunction "RH2_RED_F") (pintype "bidirectional"))
      (node (ref "U9") (pin "G") (pinfunction "RS2_RED_G") (pintype "bidirectional"))
      (node (ref "U9") (pin "H") (pinfunction "RH2_OX_H") (pintype "bidirectional"))
      (node (ref "U9") (pin "J") (pinfunction "RS2_OX_J") (pintype "bidirectional"))
    )
    (net (code "23") (name "Net-(R37-Pad2)") (class "Default")
      (node (ref "R37") (pin "2") (pinfunction "2_2") (pintype "passive"))
      (node (ref "U6") (pin "TXD") (pinfunction "TXD_TXD") (pintype "bidirectional"))
    )
    (net (code "24") (name "Net-(RELOAD-B1)") (class "Default")
      (node (ref "R13") (pin "1") (pinfunction "1_1") (pintype "passive"))
      (node (ref "RELOAD") (pin "3") (pinfunction "B1_3") (pintype "bidirectional"))
    )
    (net (code "25") (name "Net-(RESET-B1)") (class "Default")
      (node (ref "R4") (pin "1") (pinfunction "1_1") (pintype "passive"))
      (node (ref "RESET") (pin "3") (pinfunction "B1_3") (pintype "bidirectional"))
    )
    (net (code "26") (name "Net-(U2-TXD)") (class "Default")
      (node (ref "R34") (pin "2") (pinfunction "2_2") (pintype "passive"))
      (node (ref "U2") (pin "3") (pinfunction "TXD_3") (pintype "output"))
    )
    (net (code "27") (name "Net-(U2-UD+)") (class "Default")
      (node (ref "U2") (pin "6") (pinfunction "UD+_6") (pintype "bidirectional"))
      (node (ref "USB1") (pin "3") (pinfunction "D+_3") (pintype "bidirectional"))
    )
    (net (code "28") (name "Net-(U2-UD-)") (class "Default")
      (node (ref "U2") (pin "7") (pinfunction "UD-_7") (pintype "bidirectional"))
      (node (ref "USB1") (pin "2") (pinfunction "D-_2") (pintype "bidirectional"))
    )
    (net (code "29") (name "Net-(U2-XI)") (class "Default")
      (node (ref "C18") (pin "2") (pinfunction "2_2") (pintype "passive"))
      (node (ref "U2") (pin "9") (pinfunction "XI_9") (pintype "input"))
      (node (ref "Y1") (pin "2") (pinfunction "2_2") (pintype "passive"))
    )
    (net (code "30") (name "Net-(U2-XO)") (class "Default")
      (node (ref "C19") (pin "2") (pinfunction "2_2") (pintype "passive"))
      (node (ref "U2") (pin "10") (pinfunction "XO_10") (pintype "output"))
      (node (ref "Y1") (pin "1") (pinfunction "1_1") (pintype "passive"))
    )
    (net (code "31") (name "Net-(U4-RFIN)") (class "Default")
      (node (ref "L1") (pin "2") (pinfunction "2_2") (pintype "passive"))
      (node (ref "L2") (pin "P$1") (pinfunction "P$1_P$1") (pintype "passive"))
      (node (ref "U4") (pin "3") (pinfunction "RFIN_3") (pintype "bidirectional"))
    )
    (net (code "32") (name "Net-(U4-VCC)") (class "Default")
      (node (ref "C12") (pin "2") (pinfunction "2_2") (pintype "passive"))
      (node (ref "C15") (pin "2") (pinfunction "2_2") (pintype "passive"))
      (node (ref "R5") (pin "2") (pinfunction "2_2") (pintype "passive"))
      (node (ref "U4") (pin "4") (pinfunction "VCC_4") (pintype "power_in"))
    )
    (net (code "33") (name "Net-(U4-~{SHDN})") (class "Default")
      (node (ref "R6") (pin "2") (pinfunction "2_2") (pintype "passive"))
      (node (ref "U4") (pin "5") (pinfunction "~{SHDN}_5") (pintype "bidirectional"))
    )
    (net (code "34") (name "Net-(U5-RESERVED)") (class "Default")
      (node (ref "R18") (pin "2") (pinfunction "2_2") (pintype "passive"))
      (node (ref "U5") (pin "16") (pinfunction "RESERVED_16") (pintype "bidirectional"))
    )
    (net (code "35") (name "Net-(U5-RESERVED1)") (class "Default")
      (node (ref "R19") (pin "2") (pinfunction "2_2") (pintype "passive"))
      (node (ref "U5") (pin "17") (pinfunction "RESERVED1_17") (pintype "bidirectional"))
    )
    (net (code "36") (name "Net-(U5-RXD1)") (class "Default")
      (node (ref "R25") (pin "1") (pinfunction "1_1") (pintype "passive"))
      (node (ref "U5") (pin "3") (pinfunction "RXD1_3") (pintype "bidirectional"))
    )
    (net (code "37") (name "Net-(U5-TXD1)") (class "Default")
      (node (ref "R38") (pin "1") (pinfunction "1_1") (pintype "passive"))
      (node (ref "U5") (pin "2") (pinfunction "TXD1_2") (pintype "bidirectional"))
    )
    (net (code "38") (name "Net-(U5-V_BCKP)") (class "Default")
      (node (ref "BAT1") (pin "+1") (pinfunction "V+_+1") (pintype "bidirectional"))
      (node (ref "BAT1") (pin "+2") (pinfunction "V+_+2") (pintype "bidirectional"))
      (node (ref "U5") (pin "6") (pinfunction "V_BCKP_6") (pintype "bidirectional"))
    )
    (net (code "39") (name "Net-(U7-TXD0)") (class "Default")
      (node (ref "R33") (pin "2") (pinfunction "2_2") (pintype "passive"))
      (node (ref "U7") (pin "35") (pinfunction "TXD0_35") (pintype "output"))
    )
    (net (code "40") (name "Net-(U9-RH1_OX)") (class "Default")
      (node (ref "R23") (pin "2") (pinfunction "2_2") (pintype "passive"))
      (node (ref "U9") (pin "A") (pinfunction "RH1_OX_A") (pintype "bidirectional"))
    )
    (net (code "41") (name "Net-(U9-RH1_RED)") (class "Default")
      (node (ref "R21") (pin "2") (pinfunction "2_2") (pintype "passive"))
      (node (ref "U9") (pin "C") (pinfunction "RH1_RED_C") (pintype "bidirectional"))
    )
    (net (code "42") (name "Net-(USB1-VBUS)") (class "Default")
      (node (ref "L3") (pin "1") (pinfunction "1_1") (pintype "passive"))
      (node (ref "USB1") (pin "1") (pinfunction "VBUS_1") (pintype "power_in"))
    )
    (net (code "43") (name "PM_RESET") (class "Default")
      (node (ref "U6") (pin "RESET") (pinfunction "RESET_RESET") (pintype "bidirectional"))
      (node (ref "U7") (pin "10") (pinfunction "IO25/DAC1/A2_8_10") (pintype "bidirectional"))
    )
    (net (code "44") (name "PM_SET") (class "Default")
      (node (ref "U6") (pin "SET") (pinfunction "SET_SET") (pintype "bidirectional"))
      (node (ref "U7") (pin "29") (pinfunction "IO5_29") (pintype "bidirectional"))
    )
    (net (code "45") (name "RELOAD") (class "Default")
      (node (ref "C4") (pin "2") (pinfunction "2_2") (pintype "passive"))
      (node (ref "RELOAD") (pin "2") (pinfunction "B0_2") (pintype "bidirectional"))
      (node (ref "U7") (pin "4") (pinfunction "IO36/SEN_VP/A1_0_4") (pintype "passive"))
    )
    (net (code "46") (name "RESET") (class "Default")
      (node (ref "C3") (pin "2") (pinfunction "2_2") (pintype "passive"))
      (node (ref "Q3") (pin "3") (pinfunction "C_3") (pintype "passive"))
      (node (ref "RESET") (pin "2") (pinfunction "B0_2") (pintype "bidirectional"))
      (node (ref "U7") (pin "3") (pinfunction "EN_3") (pintype "input"))
    )
    (net (code "47") (name "RF_IN") (class "Default")
      (node (ref "U4") (pin "6") (pinfunction "RFOUT_6") (pintype "bidirectional"))
      (node (ref "U5") (pin "11") (pinfunction "RF_IN_11") (pintype "bidirectional"))
    )
    (net (code "48") (name "RTS") (class "Default")
      (node (ref "Q3") (pin "2") (pinfunction "E_2") (pintype "passive"))
      (node (ref "R1") (pin "1") (pinfunction "1_1") (pintype "passive"))
      (node (ref "U2") (pin "16") (pinfunction "RTS#_16") (pintype "output"))
    )
    (net (code "49") (name "RXD0") (class "Default")
      (node (ref "R34") (pin "1") (pinfunction "1_1") (pintype "passive"))
      (node (ref "U7") (pin "34") (pinfunction "RXD0_34") (pintype "input"))
    )
    (net (code "50") (name "SCL") (class "Default")
      (node (ref "R22") (pin "1") (pinfunction "1_1") (pintype "passive"))
      (node (ref "U1") (pin "6") (pinfunction "SCL_6") (pintype "input"))
      (node (ref "U7") (pin "12") (pinfunction "IO27/A2_7_12") (pintype "bidirectional"))
    )
    (net (code "51") (name "SDA") (class "Default")
      (node (ref "R10") (pin "1") (pinfunction "1_1") (pintype "passive"))
      (node (ref "U1") (pin "1") (pinfunction "SDA_1") (pintype "bidirectional"))
      (node (ref "U7") (pin "11") (pinfunction "IO26/DAC2/A2_9_11") (pintype "bidirectional"))
    )
    (net (code "52") (name "SD_CLK_IO14") (class "Default")
      (node (ref "R15") (pin "1") (pinfunction "1_1") (pintype "passive"))
      (node (ref "SD1") (pin "5") (pinfunction "SCLK_5") (pintype "bidirectional"))
      (node (ref "U7") (pin "13") (pinfunction "IO14/A2_6_13") (pintype "bidirectional"))
    )
    (net (code "53") (name "SD_CMD_IO15") (class "Default")
      (node (ref "R17") (pin "1") (pinfunction "1_1") (pintype "passive"))
      (node (ref "SD1") (pin "3") (pinfunction "DI_3") (pintype "bidirectional"))
      (node (ref "U7") (pin "23") (pinfunction "IO15/A2_3_23") (pintype "bidirectional"))
    )
    (net (code "54") (name "SD_CS_IO13") (class "Default")
      (node (ref "R8") (pin "1") (pinfunction "1_1") (pintype "passive"))
      (node (ref "SD1") (pin "2") (pinfunction "CS_2") (pintype "bidirectional"))
      (node (ref "U7") (pin "16") (pinfunction "IO13/A2_4_16") (pintype "bidirectional"))
    )
    (net (code "55") (name "SD_D0_IO2") (class "Default")
      (node (ref "R12") (pin "2") (pinfunction "2_2") (pintype "passive"))
      (node (ref "R9") (pin "1") (pinfunction "1_1") (pintype "passive"))
      (node (ref "SD1") (pin "7") (pinfunction "DO_7") (pintype "bidirectional"))
      (node (ref "U7") (pin "24") (pinfunction "IO2/A2_2_24") (pintype "bidirectional"))
    )
    (net (code "56") (name "SD_D1_IO4") (class "Default")
      (node (ref "SD1") (pin "8") (pinfunction "DATA1_8") (pintype "bidirectional"))
      (node (ref "U7") (pin "26") (pinfunction "IO4/A2_0_26") (pintype "bidirectional"))
    )
    (net (code "57") (name "SD_D2_IO12") (class "Default")
      (node (ref "SD1") (pin "1") (pinfunction "DATA2_1") (pintype "bidirectional"))
      (node (ref "U7") (pin "14") (pinfunction "IO12/A2_5_14") (pintype "bidirectional"))
    )
    (net (code "58") (name "STAT_LED1") (class "Default")
      (node (ref "R14") (pin "2") (pinfunction "2_2") (pintype "passive"))
      (node (ref "U7") (pin "33") (pinfunction "IO21_33") (pintype "bidirectional"))
    )
    (net (code "59") (name "STAT_LED2") (class "Default")
      (node (ref "R16") (pin "2") (pinfunction "2_2") (pintype "passive"))
      (node (ref "U7") (pin "31") (pinfunction "IO19_31") (pintype "bidirectional"))
    )
    (net (code "60") (name "STAT_LED3") (class "Default")
      (node (ref "R2") (pin "2") (pinfunction "2_2") (pintype "passive"))
      (node (ref "U7") (pin "30") (pinfunction "IO18_30") (pintype "bidirectional"))
    )
    (net (code "61") (name "TXD0") (class "Default")
      (node (ref "R33") (pin "1") (pinfunction "1_1") (pintype "passive"))
      (node (ref "U2") (pin "4") (pinfunction "RXD_4") (pintype "input"))
    )
    (net (code "62") (name "U2RXD") (class "Default")
      (node (ref "R37") (pin "1") (pinfunction "1_1") (pintype "passive"))
      (node (ref "U7") (pin "27") (pinfunction "IO16_27") (pintype "bidirectional"))
    )
    (net (code "63") (name "VCC_RF") (class "Default")
      (node (ref "R5") (pin "1") (pinfunction "1_1") (pintype "passive"))
      (node (ref "U5") (pin "14") (pinfunction "VCC_RF_14") (pintype "power_in"))
    )
    (net (code "64") (name "VOX_RAWA") (class "Default")
      (node (ref "R20") (pin "2") (pinfunction "2_2") (pintype "passive"))
      (node (ref "U8") (pin "3") (pinfunction "3_3") (pintype "bidirectional"))
      (node (ref "U9") (pin "B") (pinfunction "RS1_OX_B") (pintype "bidirectional"))
    )
    (net (code "65") (name "VOX_RAWB") (class "Default")
      (node (ref "U7") (pin "6") (pinfunction "I34/A1_6_6") (pintype "bidirectional"))
      (node (ref "U8") (pin "1") (pinfunction "1_1") (pintype "bidirectional"))
      (node (ref "U8") (pin "2") (pinfunction "2_2") (pintype "bidirectional"))
    )
    (net (code "66") (name "VRED_RAWA") (class "Default")
      (node (ref "R11") (pin "2") (pinfunction "2_2") (pintype "passive"))
      (node (ref "U8") (pin "5") (pinfunction "5_5") (pintype "bidirectional"))
      (node (ref "U9") (pin "D") (pinfunction "RS1_RED_D") (pintype "bidirectional"))
    )
    (net (code "67") (name "VRED_RAWB") (class "Default")
      (node (ref "U7") (pin "7") (pinfunction "I35/A1_7_7") (pintype "bidirectional"))
      (node (ref "U8") (pin "6") (pinfunction "6_6") (pintype "bidirectional"))
      (node (ref "U8") (pin "7") (pinfunction "7_7") (pintype "bidirectional"))
    )
    (net (code "68") (name "unconnected-(SD1-CDN-Pad9)") (class "Default")
      (node (ref "SD1") (pin "9") (pinfunction "CDN_9") (pintype "bidirectional"))
    )
    (net (code "69") (name "unconnected-(U2-ACT#-Pad2)") (class "Default")
      (node (ref "U2") (pin "2") (pinfunction "ACT#_2") (pintype "output"))
    )
    (net (code "70") (name "unconnected-(U2-CKO-Pad1)") (class "Default")
      (node (ref "U2") (pin "1") (pinfunction "CKO_1") (pintype "output"))
    )
    (net (code "71") (name "unconnected-(U2-CTS#-Pad11)") (class "Default")
      (node (ref "U2") (pin "11") (pinfunction "CTS#_11") (pintype "input"))
    )
    (net (code "72") (name "unconnected-(U2-DCD#-Pad14)") (class "Default")
      (node (ref "U2") (pin "14") (pinfunction "DCD#_14") (pintype "input"))
    )
    (net (code "73") (name "unconnected-(U2-DSR#-Pad12)") (class "Default")
      (node (ref "U2") (pin "12") (pinfunction "DSR#_12") (pintype "input"))
    )
    (net (code "74") (name "unconnected-(U2-NC-Pad17)") (class "Default")
      (node (ref "U2") (pin "17") (pinfunction "NC_17") (pintype "no_connect"))
    )
    (net (code "75") (name "unconnected-(U2-R232-Pad18)") (class "Default")
      (node (ref "U2") (pin "18") (pinfunction "R232_18") (pintype "input"))
    )
    (net (code "76") (name "unconnected-(U2-RI#-Pad13)") (class "Default")
      (node (ref "U2") (pin "13") (pinfunction "RI#_13") (pintype "input"))
    )
    (net (code "77") (name "unconnected-(U5-NC-Pad7)") (class "Default")
      (node (ref "U5") (pin "7") (pinfunction "NC_7") (pintype "bidirectional"))
    )
    (net (code "78") (name "unconnected-(U5-NC-Pad15)") (class "Default")
      (node (ref "U5") (pin "15") (pinfunction "NC_15") (pintype "bidirectional"))
    )
    (net (code "79") (name "unconnected-(U5-STANDBY-Pad5)") (class "Default")
      (node (ref "U5") (pin "5") (pinfunction "STANDBY_5") (pintype "bidirectional"))
    )
    (net (code "80") (name "unconnected-(U5-TIMER-Pad18)") (class "Default")
      (node (ref "U5") (pin "18") (pinfunction "TIMER_18") (pintype "bidirectional"))
    )
    (net (code "81") (name "unconnected-(U6-PadRXD)") (class "Default")
      (node (ref "U6") (pin "RXD") (pinfunction "RXD_RXD") (pintype "bidirectional"))
    )
    (net (code "82") (name "unconnected-(U7-CLK-Pad20)") (class "Default")
      (node (ref "U7") (pin "20") (pinfunction "CLK_20") (pintype "bidirectional"))
    )
    (net (code "83") (name "unconnected-(U7-CMD-Pad19)") (class "Default")
      (node (ref "U7") (pin "19") (pinfunction "CMD_19") (pintype "bidirectional"))
    )
    (net (code "84") (name "unconnected-(U7-IO17-Pad28)") (class "Default")
      (node (ref "U7") (pin "28") (pinfunction "IO17_28") (pintype "bidirectional"))
    )
    (net (code "85") (name "unconnected-(U7-SD0-Pad21)") (class "Default")
      (node (ref "U7") (pin "21") (pinfunction "SD0_21") (pintype "bidirectional"))
    )
    (net (code "86") (name "unconnected-(U7-SD1-Pad22)") (class "Default")
      (node (ref "U7") (pin "22") (pinfunction "SD1_22") (pintype "bidirectional"))
    )
    (net (code "87") (name "unconnected-(U7-SD2-Pad17)") (class "Default")
      (node (ref "U7") (pin "17") (pinfunction "SD2_17") (pintype "bidirectional"))
    )
    (net (code "88") (name "unconnected-(U7-SD3-Pad18)") (class "Default")
      (node (ref "U7") (pin "18") (pinfunction "SD3_18") (pintype "bidirectional"))
    )
    (net (code "89") (name "unconnected-(USB1-ID-Pad4)") (class "Default")
      (node (ref "USB1") (pin "4") (pinfunction "ID_4") (pintype "bidirectional"))
    )
  )
)
